# HHModules.net
KiCad netlist of a schematic drawn in EAGLE
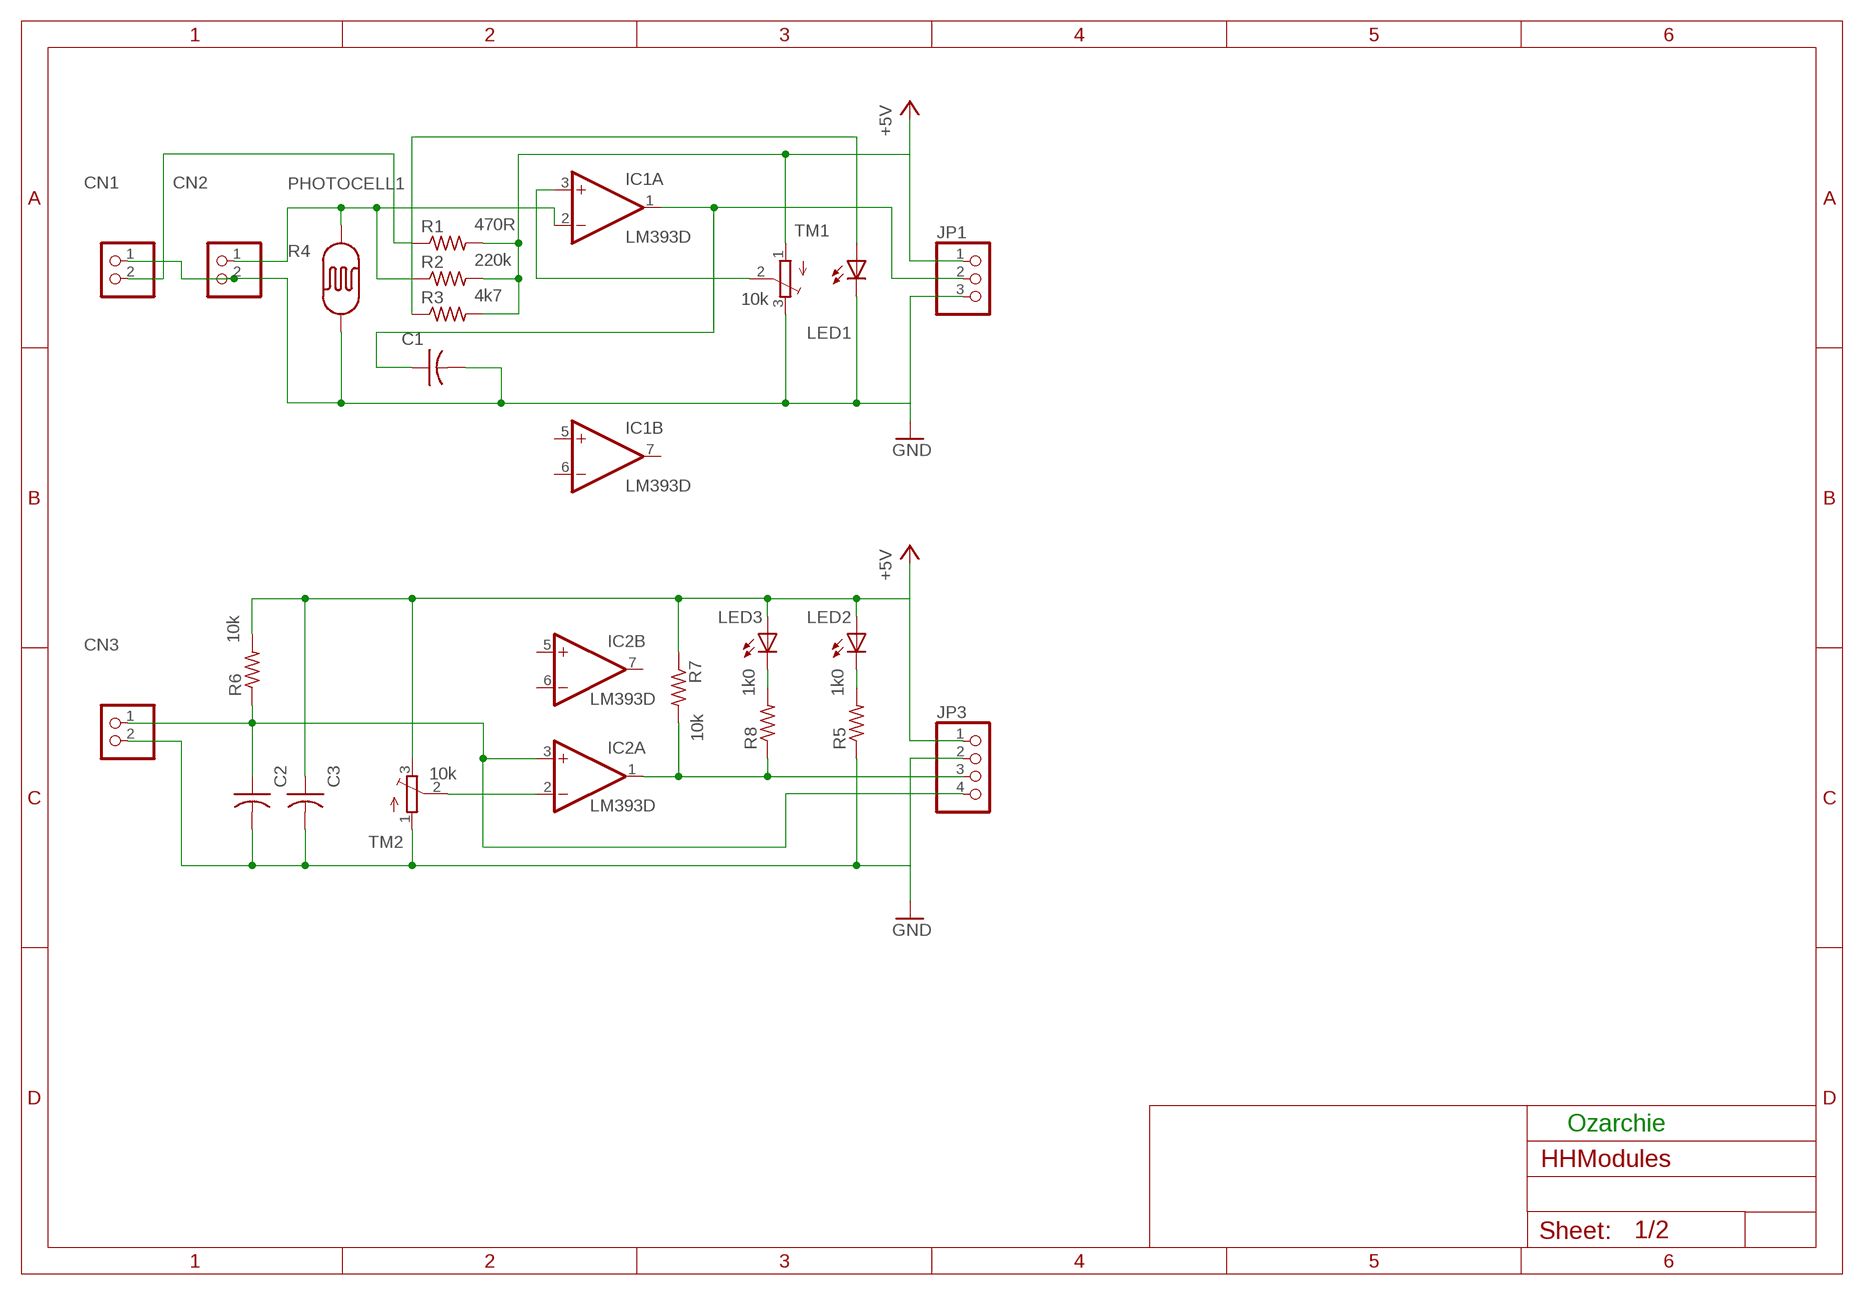
[diagram p0: schematic, sheet 1]
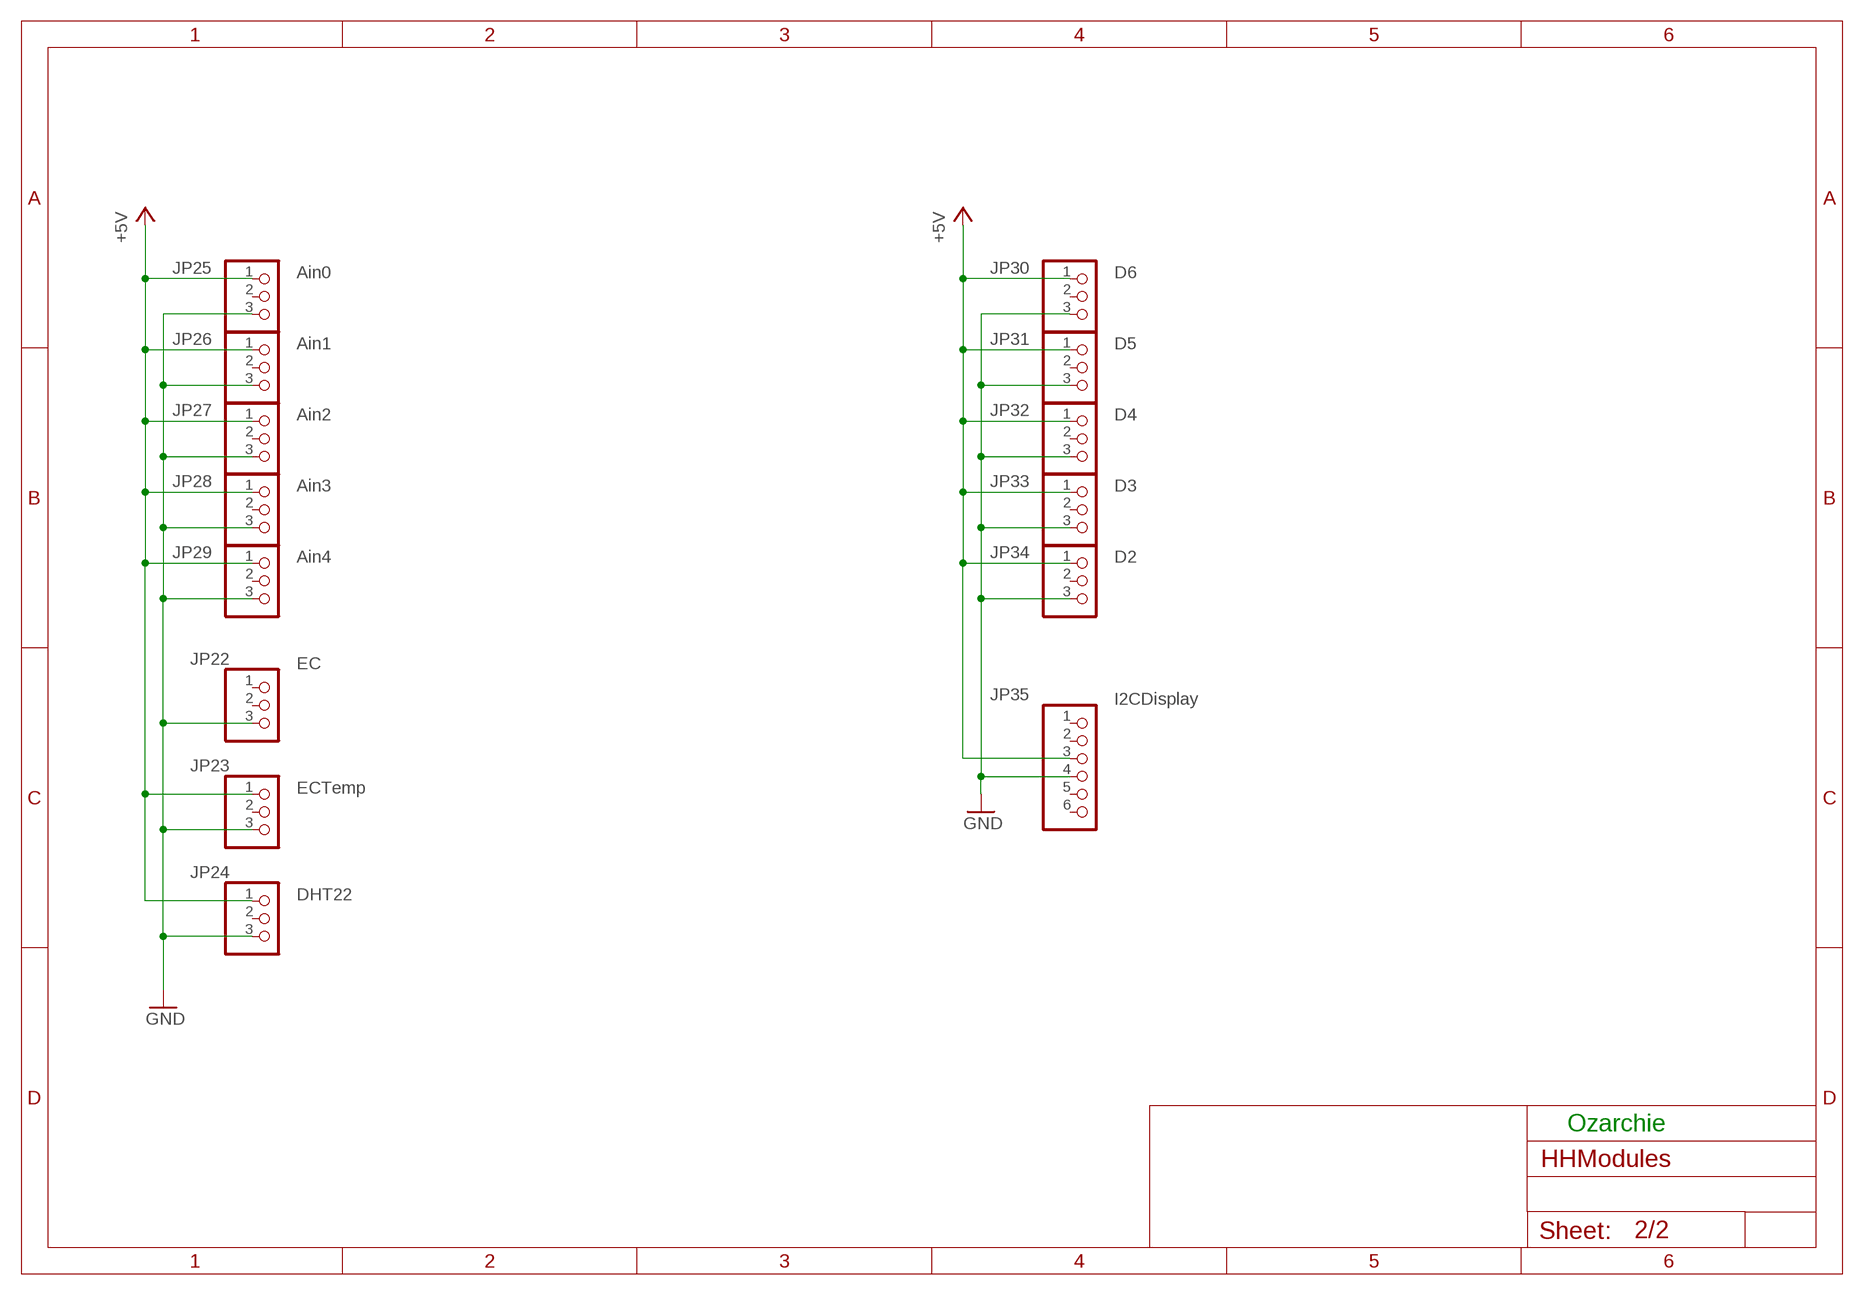
[diagram p1: schematic, sheet 2]

(export (version "E")
  (design (tool "Eeschema 10.0.6"))
  (components
    (comp (ref "C1")
      (value "C-USC0805K")
      (footprint "eagle-import:C0805K")
      (libsource (lib "eagle-import") (part "C-USC0805K"))
    )
    (comp (ref "C2")
      (value "C-USC0805K")
      (footprint "eagle-import:C0805K")
      (libsource (lib "eagle-import") (part "C-USC0805K"))
    )
    (comp (ref "C3")
      (value "C-USC0805K")
      (footprint "eagle-import:C0805K")
      (libsource (lib "eagle-import") (part "C-USC0805K"))
    )
    (comp (ref "CN1")
      (value "JST_2PIN-THM")
      (footprint "eagle-import:JST-PH-2-THM")
      (libsource (lib "eagle-import") (part "JST_2PIN-THM"))
    )
    (comp (ref "CN2")
      (value "JST_2PIN-THM")
      (footprint "eagle-import:JST-PH-2-THM")
      (libsource (lib "eagle-import") (part "JST_2PIN-THM"))
    )
    (comp (ref "CN3")
      (value "JST_2PIN-THM")
      (footprint "eagle-import:JST-PH-2-THM")
      (libsource (lib "eagle-import") (part "JST_2PIN-THM"))
    )
    (comp (ref "IC1")
      (value "LM393D")
      (footprint "eagle-import:SO08")
      (libsource (lib "eagle-import") (part "LM393D"))
    )
    (comp (ref "IC2")
      (value "LM393D")
      (footprint "eagle-import:SO08")
      (libsource (lib "eagle-import") (part "LM393D"))
    )
    (comp (ref "JP1")
      (value "PINHD-1X3")
      (footprint "eagle-import:1X03")
      (libsource (lib "eagle-import") (part "PINHD-1X3"))
    )
    (comp (ref "JP3")
      (value "PINHD-1X4")
      (footprint "eagle-import:1X04")
      (libsource (lib "eagle-import") (part "PINHD-1X4"))
    )
    (comp (ref "LED1")
      (value "LEDCHIPLED_1206")
      (footprint "eagle-import:CHIPLED_1206")
      (libsource (lib "eagle-import") (part "LEDCHIPLED_1206"))
    )
    (comp (ref "LED2")
      (value "LEDCHIPLED_1206")
      (footprint "eagle-import:CHIPLED_1206")
      (libsource (lib "eagle-import") (part "LEDCHIPLED_1206"))
    )
    (comp (ref "LED3")
      (value "LEDCHIPLED_1206")
      (footprint "eagle-import:CHIPLED_1206")
      (libsource (lib "eagle-import") (part "LEDCHIPLED_1206"))
    )
    (comp (ref "R1")
      (value "470R")
      (footprint "eagle-import:M1206")
      (libsource (lib "eagle-import") (part "R-US_M1206"))
    )
    (comp (ref "R2")
      (value "220k")
      (footprint "eagle-import:M1206")
      (libsource (lib "eagle-import") (part "R-US_M1206"))
    )
    (comp (ref "R3")
      (value "4k7")
      (footprint "eagle-import:M1206")
      (libsource (lib "eagle-import") (part "R-US_M1206"))
    )
    (comp (ref "R4")
      (value "PHOTOCELL1")
      (footprint "eagle-import:LDR_OFFBOARD")
      (libsource (lib "eagle-import") (part "PHOTOCELL1"))
    )
    (comp (ref "R5")
      (value "1k0")
      (footprint "eagle-import:M1206")
      (libsource (lib "eagle-import") (part "R-US_M1206"))
    )
    (comp (ref "R6")
      (value "10k")
      (footprint "eagle-import:M1206")
      (libsource (lib "eagle-import") (part "R-US_M1206"))
    )
    (comp (ref "R7")
      (value "10k")
      (footprint "eagle-import:M1206")
      (libsource (lib "eagle-import") (part "R-US_M1206"))
    )
    (comp (ref "R8")
      (value "1k0")
      (footprint "eagle-import:M1206")
      (libsource (lib "eagle-import") (part "R-US_M1206"))
    )
    (comp (ref "TM1")
      (value "10k")
      (footprint "eagle-import:TRIM-3386")
      (libsource (lib "eagle-import") (part "TRIMPOT3386"))
    )
    (comp (ref "TM2")
      (value "10k")
      (footprint "eagle-import:TRIM-3386")
      (libsource (lib "eagle-import") (part "TRIMPOT3386"))
    )
    (comp (ref "JP22")
      (value "EC")
      (footprint "eagle-import:1X03")
      (libsource (lib "eagle-import") (part "PINHD-1X3"))
    )
    (comp (ref "JP23")
      (value "ECTemp")
      (footprint "eagle-import:1X03")
      (libsource (lib "eagle-import") (part "PINHD-1X3"))
    )
    (comp (ref "JP24")
      (value "DHT22")
      (footprint "eagle-import:1X03")
      (libsource (lib "eagle-import") (part "PINHD-1X3"))
    )
    (comp (ref "JP25")
      (value "Ain0")
      (footprint "eagle-import:1X03")
      (libsource (lib "eagle-import") (part "PINHD-1X3"))
    )
    (comp (ref "JP26")
      (value "Ain1")
      (footprint "eagle-import:1X03")
      (libsource (lib "eagle-import") (part "PINHD-1X3"))
    )
    (comp (ref "JP27")
      (value "Ain2")
      (footprint "eagle-import:1X03")
      (libsource (lib "eagle-import") (part "PINHD-1X3"))
    )
    (comp (ref "JP28")
      (value "Ain3")
      (footprint "eagle-import:1X03")
      (libsource (lib "eagle-import") (part "PINHD-1X3"))
    )
    (comp (ref "JP29")
      (value "Ain4")
      (footprint "eagle-import:1X03")
      (libsource (lib "eagle-import") (part "PINHD-1X3"))
    )
    (comp (ref "JP30")
      (value "D6")
      (footprint "eagle-import:1X03")
      (libsource (lib "eagle-import") (part "PINHD-1X3"))
    )
    (comp (ref "JP31")
      (value "D5")
      (footprint "eagle-import:1X03")
      (libsource (lib "eagle-import") (part "PINHD-1X3"))
    )
    (comp (ref "JP32")
      (value "D4")
      (footprint "eagle-import:1X03")
      (libsource (lib "eagle-import") (part "PINHD-1X3"))
    )
    (comp (ref "JP33")
      (value "D3")
      (footprint "eagle-import:1X03")
      (libsource (lib "eagle-import") (part "PINHD-1X3"))
    )
    (comp (ref "JP34")
      (value "D2")
      (footprint "eagle-import:1X03")
      (libsource (lib "eagle-import") (part "PINHD-1X3"))
    )
    (comp (ref "JP35")
      (value "I2CDisplay")
      (footprint "eagle-import:1X06")
      (libsource (lib "eagle-import") (part "PINHD-1X6"))
    )
  )
  (nets
    (net (code "1") (name "+5V") (class "Default")
      (node (ref "C3") (pin "1") (pinfunction "1_1") (pintype "passive"))
      (node (ref "JP1") (pin "1") (pinfunction "1_1") (pintype "passive"))
      (node (ref "JP23") (pin "1") (pinfunction "1_1") (pintype "passive"))
      (node (ref "JP24") (pin "1") (pinfunction "1_1") (pintype "passive"))
      (node (ref "JP25") (pin "1") (pinfunction "1_1") (pintype "passive"))
      (node (ref "JP26") (pin "1") (pinfunction "1_1") (pintype "passive"))
      (node (ref "JP27") (pin "1") (pinfunction "1_1") (pintype "passive"))
      (node (ref "JP28") (pin "1") (pinfunction "1_1") (pintype "passive"))
      (node (ref "JP29") (pin "1") (pinfunction "1_1") (pintype "passive"))
      (node (ref "JP3") (pin "1") (pinfunction "1_1") (pintype "passive"))
      (node (ref "JP30") (pin "1") (pinfunction "1_1") (pintype "passive"))
      (node (ref "JP31") (pin "1") (pinfunction "1_1") (pintype "passive"))
      (node (ref "JP32") (pin "1") (pinfunction "1_1") (pintype "passive"))
      (node (ref "JP33") (pin "1") (pinfunction "1_1") (pintype "passive"))
      (node (ref "JP34") (pin "1") (pinfunction "1_1") (pintype "passive"))
      (node (ref "JP35") (pin "3") (pinfunction "3_3") (pintype "passive"))
      (node (ref "LED2") (pin "A") (pinfunction "A_A") (pintype "passive"))
      (node (ref "LED3") (pin "A") (pinfunction "A_A") (pintype "passive"))
      (node (ref "R1") (pin "2") (pinfunction "2_2") (pintype "passive"))
      (node (ref "R2") (pin "2") (pinfunction "2_2") (pintype "passive"))
      (node (ref "R3") (pin "2") (pinfunction "2_2") (pintype "passive"))
      (node (ref "R6") (pin "2") (pinfunction "2_2") (pintype "passive"))
      (node (ref "R7") (pin "1") (pinfunction "1_1") (pintype "passive"))
      (node (ref "TM1") (pin "1") (pinfunction "A_1") (pintype "passive"))
      (node (ref "TM2") (pin "3") (pinfunction "E_3") (pintype "passive"))
    )
    (net (code "2") (name "GND") (class "Default")
      (node (ref "C1") (pin "2") (pinfunction "2_2") (pintype "passive"))
      (node (ref "C2") (pin "2") (pinfunction "2_2") (pintype "passive"))
      (node (ref "C3") (pin "2") (pinfunction "2_2") (pintype "passive"))
      (node (ref "CN1") (pin "1") (pinfunction "2_1") (pintype "passive"))
      (node (ref "CN2") (pin "2") (pinfunction "1_2") (pintype "passive"))
      (node (ref "CN3") (pin "2") (pinfunction "1_2") (pintype "passive"))
      (node (ref "JP1") (pin "3") (pinfunction "3_3") (pintype "passive"))
      (node (ref "JP22") (pin "3") (pinfunction "3_3") (pintype "passive"))
      (node (ref "JP23") (pin "3") (pinfunction "3_3") (pintype "passive"))
      (node (ref "JP24") (pin "3") (pinfunction "3_3") (pintype "passive"))
      (node (ref "JP25") (pin "3") (pinfunction "3_3") (pintype "passive"))
      (node (ref "JP26") (pin "3") (pinfunction "3_3") (pintype "passive"))
      (node (ref "JP27") (pin "3") (pinfunction "3_3") (pintype "passive"))
      (node (ref "JP28") (pin "3") (pinfunction "3_3") (pintype "passive"))
      (node (ref "JP29") (pin "3") (pinfunction "3_3") (pintype "passive"))
      (node (ref "JP3") (pin "2") (pinfunction "2_2") (pintype "passive"))
      (node (ref "JP30") (pin "3") (pinfunction "3_3") (pintype "passive"))
      (node (ref "JP31") (pin "3") (pinfunction "3_3") (pintype "passive"))
      (node (ref "JP32") (pin "3") (pinfunction "3_3") (pintype "passive"))
      (node (ref "JP33") (pin "3") (pinfunction "3_3") (pintype "passive"))
      (node (ref "JP34") (pin "3") (pinfunction "3_3") (pintype "passive"))
      (node (ref "JP35") (pin "4") (pinfunction "4_4") (pintype "passive"))
      (node (ref "LED1") (pin "C") (pinfunction "C_C") (pintype "passive"))
      (node (ref "R4") (pin "1") (pinfunction "P$1_1") (pintype "bidirectional"))
      (node (ref "R5") (pin "1") (pinfunction "1_1") (pintype "passive"))
      (node (ref "TM1") (pin "3") (pinfunction "E_3") (pintype "passive"))
      (node (ref "TM2") (pin "1") (pinfunction "A_1") (pintype "passive"))
    )
    (net (code "3") (name "Net-(CN1-1)") (class "Default")
      (node (ref "CN1") (pin "2") (pinfunction "1_2") (pintype "passive"))
      (node (ref "R1") (pin "1") (pinfunction "1_1") (pintype "passive"))
    )
    (net (code "4") (name "Net-(CN2-2)") (class "Default")
      (node (ref "CN2") (pin "1") (pinfunction "2_1") (pintype "passive"))
      (node (ref "IC1") (pin "2") (pinfunction "-IN_2") (pintype "input"))
      (node (ref "R2") (pin "1") (pinfunction "1_1") (pintype "passive"))
      (node (ref "R4") (pin "2") (pinfunction "P$2_2") (pintype "bidirectional"))
    )
    (net (code "5") (name "Net-(CN3-2)") (class "Default")
      (node (ref "C2") (pin "1") (pinfunction "1_1") (pintype "passive"))
      (node (ref "CN3") (pin "1") (pinfunction "2_1") (pintype "passive"))
      (node (ref "IC2") (pin "3") (pinfunction "+IN_3") (pintype "input"))
      (node (ref "JP3") (pin "4") (pinfunction "4_4") (pintype "passive"))
      (node (ref "R6") (pin "1") (pinfunction "1_1") (pintype "passive"))
    )
    (net (code "6") (name "Net-(IC1A-+IN)") (class "Default")
      (node (ref "IC1") (pin "3") (pinfunction "+IN_3") (pintype "input"))
      (node (ref "TM1") (pin "2") (pinfunction "S_2") (pintype "passive"))
    )
    (net (code "7") (name "Net-(IC1A-OUT)") (class "Default")
      (node (ref "C1") (pin "1") (pinfunction "1_1") (pintype "passive"))
      (node (ref "IC1") (pin "1") (pinfunction "OUT_1") (pintype "output"))
      (node (ref "JP1") (pin "2") (pinfunction "2_2") (pintype "passive"))
    )
    (net (code "8") (name "Net-(IC2A--IN)") (class "Default")
      (node (ref "IC2") (pin "2") (pinfunction "-IN_2") (pintype "input"))
      (node (ref "TM2") (pin "2") (pinfunction "S_2") (pintype "passive"))
    )
    (net (code "9") (name "Net-(IC2A-OUT)") (class "Default")
      (node (ref "IC2") (pin "1") (pinfunction "OUT_1") (pintype "output"))
      (node (ref "JP3") (pin "3") (pinfunction "3_3") (pintype "passive"))
      (node (ref "R7") (pin "2") (pinfunction "2_2") (pintype "passive"))
      (node (ref "R8") (pin "1") (pinfunction "1_1") (pintype "passive"))
    )
    (net (code "10") (name "Net-(LED1-PadA)") (class "Default")
      (node (ref "LED1") (pin "A") (pinfunction "A_A") (pintype "passive"))
      (node (ref "R3") (pin "1") (pinfunction "1_1") (pintype "passive"))
    )
    (net (code "11") (name "Net-(LED2-PadC)") (class "Default")
      (node (ref "LED2") (pin "C") (pinfunction "C_C") (pintype "passive"))
      (node (ref "R5") (pin "2") (pinfunction "2_2") (pintype "passive"))
    )
    (net (code "12") (name "Net-(LED3-PadC)") (class "Default")
      (node (ref "LED3") (pin "C") (pinfunction "C_C") (pintype "passive"))
      (node (ref "R8") (pin "2") (pinfunction "2_2") (pintype "passive"))
    )
    (net (code "13") (name "unconnected-(IC1B-+IN-Pad5)") (class "Default")
      (node (ref "IC1") (pin "5") (pinfunction "+IN_5") (pintype "input"))
    )
    (net (code "14") (name "unconnected-(IC1B--IN-Pad6)") (class "Default")
      (node (ref "IC1") (pin "6") (pinfunction "-IN_6") (pintype "input"))
    )
    (net (code "15") (name "unconnected-(IC1B-OUT-Pad7)") (class "Default")
      (node (ref "IC1") (pin "7") (pinfunction "OUT_7") (pintype "output"))
    )
    (net (code "16") (name "unconnected-(IC2B-+IN-Pad5)") (class "Default")
      (node (ref "IC2") (pin "5") (pinfunction "+IN_5") (pintype "input"))
    )
    (net (code "17") (name "unconnected-(IC2B--IN-Pad6)") (class "Default")
      (node (ref "IC2") (pin "6") (pinfunction "-IN_6") (pintype "input"))
    )
    (net (code "18") (name "unconnected-(IC2B-OUT-Pad7)") (class "Default")
      (node (ref "IC2") (pin "7") (pinfunction "OUT_7") (pintype "output"))
    )
    (net (code "19") (name "unconnected-(JP22-Pad1)") (class "Default")
      (node (ref "JP22") (pin "1") (pinfunction "1_1") (pintype "passive"))
    )
    (net (code "20") (name "unconnected-(JP22-Pad2)") (class "Default")
      (node (ref "JP22") (pin "2") (pinfunction "2_2") (pintype "passive"))
    )
    (net (code "21") (name "unconnected-(JP23-Pad2)") (class "Default")
      (node (ref "JP23") (pin "2") (pinfunction "2_2") (pintype "passive"))
    )
    (net (code "22") (name "unconnected-(JP24-Pad2)") (class "Default")
      (node (ref "JP24") (pin "2") (pinfunction "2_2") (pintype "passive"))
    )
    (net (code "23") (name "unconnected-(JP25-Pad2)") (class "Default")
      (node (ref "JP25") (pin "2") (pinfunction "2_2") (pintype "passive"))
    )
    (net (code "24") (name "unconnected-(JP26-Pad2)") (class "Default")
      (node (ref "JP26") (pin "2") (pinfunction "2_2") (pintype "passive"))
    )
    (net (code "25") (name "unconnected-(JP27-Pad2)") (class "Default")
      (node (ref "JP27") (pin "2") (pinfunction "2_2") (pintype "passive"))
    )
    (net (code "26") (name "unconnected-(JP28-Pad2)") (class "Default")
      (node (ref "JP28") (pin "2") (pinfunction "2_2") (pintype "passive"))
    )
    (net (code "27") (name "unconnected-(JP29-Pad2)") (class "Default")
      (node (ref "JP29") (pin "2") (pinfunction "2_2") (pintype "passive"))
    )
    (net (code "28") (name "unconnected-(JP30-Pad2)") (class "Default")
      (node (ref "JP30") (pin "2") (pinfunction "2_2") (pintype "passive"))
    )
    (net (code "29") (name "unconnected-(JP31-Pad2)") (class "Default")
      (node (ref "JP31") (pin "2") (pinfunction "2_2") (pintype "passive"))
    )
    (net (code "30") (name "unconnected-(JP32-Pad2)") (class "Default")
      (node (ref "JP32") (pin "2") (pinfunction "2_2") (pintype "passive"))
    )
    (net (code "31") (name "unconnected-(JP33-Pad2)") (class "Default")
      (node (ref "JP33") (pin "2") (pinfunction "2_2") (pintype "passive"))
    )
    (net (code "32") (name "unconnected-(JP34-Pad2)") (class "Default")
      (node (ref "JP34") (pin "2") (pinfunction "2_2") (pintype "passive"))
    )
    (net (code "33") (name "unconnected-(JP35-Pad1)") (class "Default")
      (node (ref "JP35") (pin "1") (pinfunction "1_1") (pintype "passive"))
    )
    (net (code "34") (name "unconnected-(JP35-Pad2)") (class "Default")
      (node (ref "JP35") (pin "2") (pinfunction "2_2") (pintype "passive"))
    )
    (net (code "35") (name "unconnected-(JP35-Pad5)") (class "Default")
      (node (ref "JP35") (pin "5") (pinfunction "5_5") (pintype "passive"))
    )
    (net (code "36") (name "unconnected-(JP35-Pad6)") (class "Default")
      (node (ref "JP35") (pin "6") (pinfunction "6_6") (pintype "passive"))
    )
  )
)
